# SGP30_Rev_C.net
KiCad netlist of a schematic drawn in EAGLE
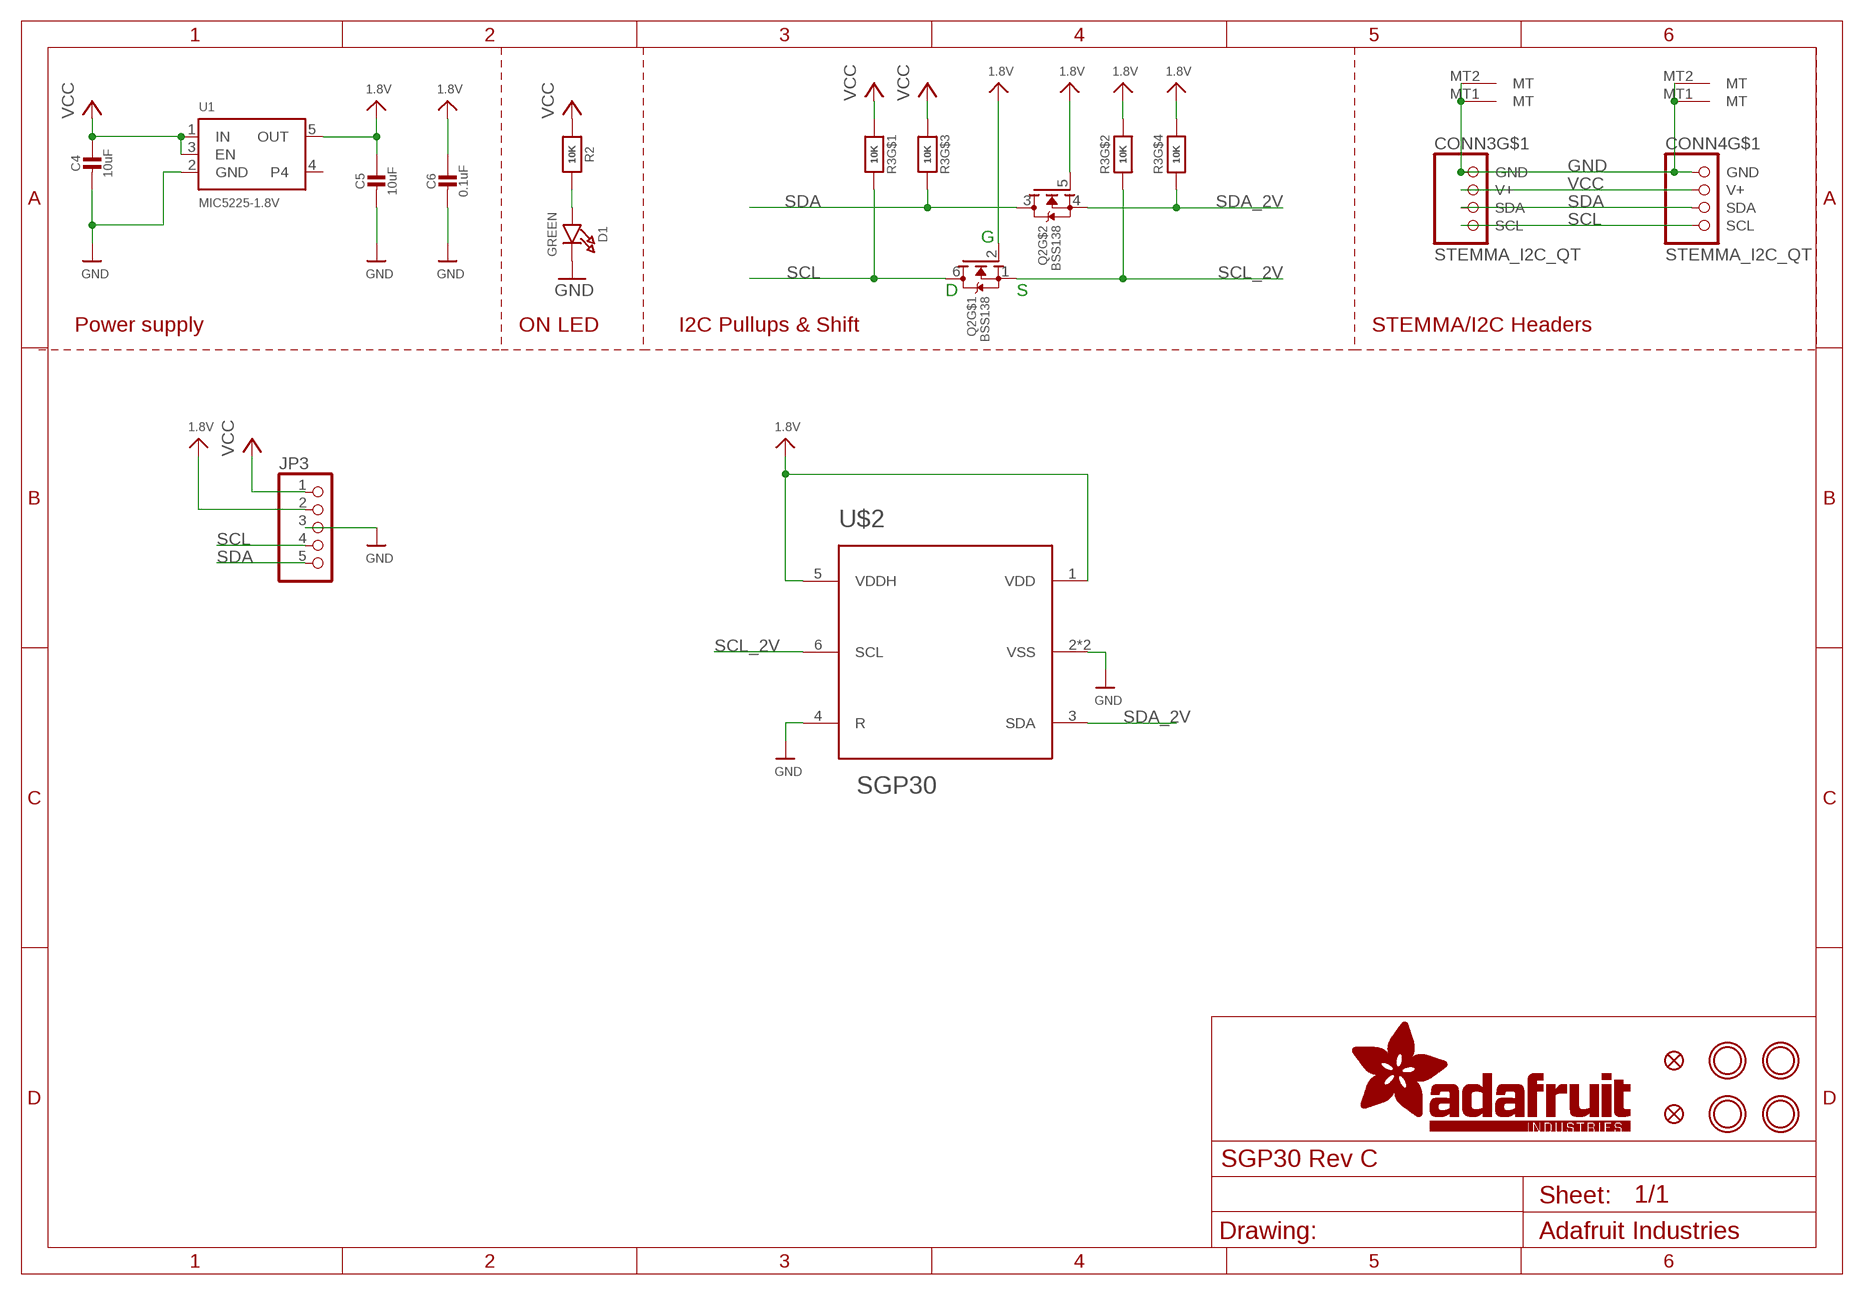
[diagram p0: schematic, sheet 1]

(export (version "E")
  (design (tool "Eeschema 10.0.6"))
  (components
    (comp (ref "C4")
      (value "10uF")
      (footprint "eagle-import:0805-NO")
      (libsource (lib "eagle-import") (part "CAP_CERAMIC0805-NOOUTLINE"))
    )
    (comp (ref "C5")
      (value "10uF")
      (footprint "eagle-import:0805-NO")
      (libsource (lib "eagle-import") (part "CAP_CERAMIC0805-NOOUTLINE"))
    )
    (comp (ref "C6")
      (value "0.1uF")
      (footprint "eagle-import:0603-NO")
      (libsource (lib "eagle-import") (part "CAP_CERAMIC0603_NO"))
    )
    (comp (ref "CONN3")
      (value "STEMMA_I2C_QT")
      (footprint "eagle-import:JST_SH4")
      (libsource (lib "eagle-import") (part "STEMMA_I2C_QT"))
    )
    (comp (ref "CONN4")
      (value "STEMMA_I2C_QT")
      (footprint "eagle-import:JST_SH4")
      (libsource (lib "eagle-import") (part "STEMMA_I2C_QT"))
    )
    (comp (ref "D1")
      (value "GREEN")
      (footprint "eagle-import:CHIPLED_0603_NOOUTLINE")
      (libsource (lib "eagle-import") (part "LED0603_NOOUTLINE"))
    )
    (comp (ref "FID3")
      (value "FIDUCIAL_1MM")
      (footprint "eagle-import:FIDUCIAL_1MM")
      (libsource (lib "eagle-import") (part "FIDUCIAL_1MM"))
    )
    (comp (ref "FID4")
      (value "FIDUCIAL_1MM")
      (footprint "eagle-import:FIDUCIAL_1MM")
      (libsource (lib "eagle-import") (part "FIDUCIAL_1MM"))
    )
    (comp (ref "JP3")
      (value "HEADER-1X570MIL")
      (footprint "eagle-import:1X05_ROUND_70")
      (libsource (lib "eagle-import") (part "HEADER-1X570MIL"))
    )
    (comp (ref "Q2")
      (value "BSS138")
      (footprint "eagle-import:SOT363")
      (libsource (lib "eagle-import") (part "MOSFET-N_DUAL"))
    )
    (comp (ref "R2")
      (value "10K")
      (footprint "eagle-import:0603-NO")
      (libsource (lib "eagle-import") (part "RESISTOR_0603_NOOUT"))
    )
    (comp (ref "R3")
      (value "10K")
      (footprint "eagle-import:RESPACK_4X0603")
      (libsource (lib "eagle-import") (part "RESISTOR_4PACK"))
    )
    (comp (ref "U$2")
      (value "SGP30")
      (footprint "eagle-import:SGP30")
      (libsource (lib "eagle-import") (part "SGP30"))
    )
    (comp (ref "U$28")
      (value "MOUNTINGHOLE2.5")
      (footprint "eagle-import:MOUNTINGHOLE_2.5_PLATED")
      (libsource (lib "eagle-import") (part "MOUNTINGHOLE2.5"))
    )
    (comp (ref "U$29")
      (value "MOUNTINGHOLE2.5")
      (footprint "eagle-import:MOUNTINGHOLE_2.5_PLATED")
      (libsource (lib "eagle-import") (part "MOUNTINGHOLE2.5"))
    )
    (comp (ref "U$31")
      (value "MOUNTINGHOLE2.5")
      (footprint "eagle-import:MOUNTINGHOLE_2.5_PLATED")
      (libsource (lib "eagle-import") (part "MOUNTINGHOLE2.5"))
    )
    (comp (ref "U$32")
      (value "MOUNTINGHOLE2.5")
      (footprint "eagle-import:MOUNTINGHOLE_2.5_PLATED")
      (libsource (lib "eagle-import") (part "MOUNTINGHOLE2.5"))
    )
    (comp (ref "U1")
      (value "MIC5225-1.8V")
      (footprint "eagle-import:SOT23-5")
      (libsource (lib "eagle-import") (part "VREG_SOT23-5"))
    )
  )
  (nets
    (net (code "1") (name "/SCL") (class "Default")
      (node (ref "CONN3") (pin "4") (pinfunction "SCL_4") (pintype "passive"))
      (node (ref "CONN4") (pin "4") (pinfunction "SCL_4") (pintype "passive"))
      (node (ref "JP3") (pin "4") (pinfunction "4_4") (pintype "passive"))
      (node (ref "Q2") (pin "6") (pinfunction "D_6") (pintype "bidirectional"))
      (node (ref "R3") (pin "8") (pinfunction "2_8") (pintype "passive"))
    )
    (net (code "2") (name "/SCL_2V") (class "Default")
      (node (ref "Q2") (pin "1") (pinfunction "S_1") (pintype "bidirectional"))
      (node (ref "R3") (pin "7") (pinfunction "2_7") (pintype "passive"))
      (node (ref "U$2") (pin "6") (pinfunction "SCL_6") (pintype "bidirectional"))
    )
    (net (code "3") (name "/SDA") (class "Default")
      (node (ref "CONN3") (pin "3") (pinfunction "SDA_3") (pintype "passive"))
      (node (ref "CONN4") (pin "3") (pinfunction "SDA_3") (pintype "passive"))
      (node (ref "JP3") (pin "5") (pinfunction "5_5") (pintype "passive"))
      (node (ref "Q2") (pin "3") (pinfunction "D_3") (pintype "bidirectional"))
      (node (ref "R3") (pin "6") (pinfunction "2_6") (pintype "passive"))
    )
    (net (code "4") (name "/SDA_2V") (class "Default")
      (node (ref "Q2") (pin "4") (pinfunction "S_4") (pintype "bidirectional"))
      (node (ref "R3") (pin "5") (pinfunction "2_5") (pintype "passive"))
      (node (ref "U$2") (pin "3") (pinfunction "SDA_3") (pintype "bidirectional"))
    )
    (net (code "5") (name "1.8V") (class "Default")
      (node (ref "C5") (pin "1") (pinfunction "1_1") (pintype "passive"))
      (node (ref "C6") (pin "1") (pinfunction "1_1") (pintype "passive"))
      (node (ref "JP3") (pin "2") (pinfunction "2_2") (pintype "passive"))
      (node (ref "Q2") (pin "2") (pinfunction "G_2") (pintype "bidirectional"))
      (node (ref "Q2") (pin "5") (pinfunction "G_5") (pintype "bidirectional"))
      (node (ref "R3") (pin "2") (pinfunction "1_2") (pintype "passive"))
      (node (ref "R3") (pin "4") (pinfunction "1_4") (pintype "passive"))
      (node (ref "U$2") (pin "1") (pinfunction "VDD_1") (pintype "bidirectional"))
      (node (ref "U$2") (pin "5") (pinfunction "VDDH_5") (pintype "bidirectional"))
      (node (ref "U1") (pin "5") (pinfunction "OUT_5") (pintype "power_in"))
    )
    (net (code "6") (name "GND") (class "Default")
      (node (ref "C4") (pin "2") (pinfunction "2_2") (pintype "passive"))
      (node (ref "C5") (pin "2") (pinfunction "2_2") (pintype "passive"))
      (node (ref "C6") (pin "2") (pinfunction "2_2") (pintype "passive"))
      (node (ref "CONN3") (pin "1") (pinfunction "GND_1") (pintype "passive"))
      (node (ref "CONN3") (pin "MT1") (pinfunction "MT_MT1") (pintype "bidirectional"))
      (node (ref "CONN3") (pin "MT2") (pinfunction "MT_MT2") (pintype "bidirectional"))
      (node (ref "CONN4") (pin "1") (pinfunction "GND_1") (pintype "passive"))
      (node (ref "CONN4") (pin "MT1") (pinfunction "MT_MT1") (pintype "bidirectional"))
      (node (ref "CONN4") (pin "MT2") (pinfunction "MT_MT2") (pintype "bidirectional"))
      (node (ref "D1") (pin "C") (pinfunction "C_C") (pintype "passive"))
      (node (ref "JP3") (pin "3") (pinfunction "3_3") (pintype "passive"))
      (node (ref "U$2") (pin "2") (pinfunction "VSS_2") (pintype "bidirectional"))
      (node (ref "U$2") (pin "4") (pinfunction "R_4") (pintype "bidirectional"))
      (node (ref "U$2") (pin "P$7") (pinfunction "VSS_P$7") (pintype "bidirectional"))
      (node (ref "U1") (pin "2") (pinfunction "GND_2") (pintype "power_in"))
    )
    (net (code "7") (name "Net-(D1-PadA)") (class "Default")
      (node (ref "D1") (pin "A") (pinfunction "A_A") (pintype "passive"))
      (node (ref "R2") (pin "2") (pinfunction "2_2") (pintype "passive"))
    )
    (net (code "8") (name "VCC") (class "Default")
      (node (ref "C4") (pin "1") (pinfunction "1_1") (pintype "passive"))
      (node (ref "CONN3") (pin "2") (pinfunction "V+_2") (pintype "passive"))
      (node (ref "CONN4") (pin "2") (pinfunction "V+_2") (pintype "passive"))
      (node (ref "JP3") (pin "1") (pinfunction "1_1") (pintype "passive"))
      (node (ref "R2") (pin "1") (pinfunction "1_1") (pintype "passive"))
      (node (ref "R3") (pin "1") (pinfunction "1_1") (pintype "passive"))
      (node (ref "R3") (pin "3") (pinfunction "1_3") (pintype "passive"))
      (node (ref "U1") (pin "1") (pinfunction "IN_1") (pintype "power_in"))
      (node (ref "U1") (pin "3") (pinfunction "EN_3") (pintype "input"))
    )
    (net (code "9") (name "unconnected-(U1-P4-Pad4)") (class "Default")
      (node (ref "U1") (pin "4") (pinfunction "P4_4") (pintype "bidirectional"))
    )
  )
)
